# Sheet1.net
KiCad netlist of a schematic drawn in Altium Designer
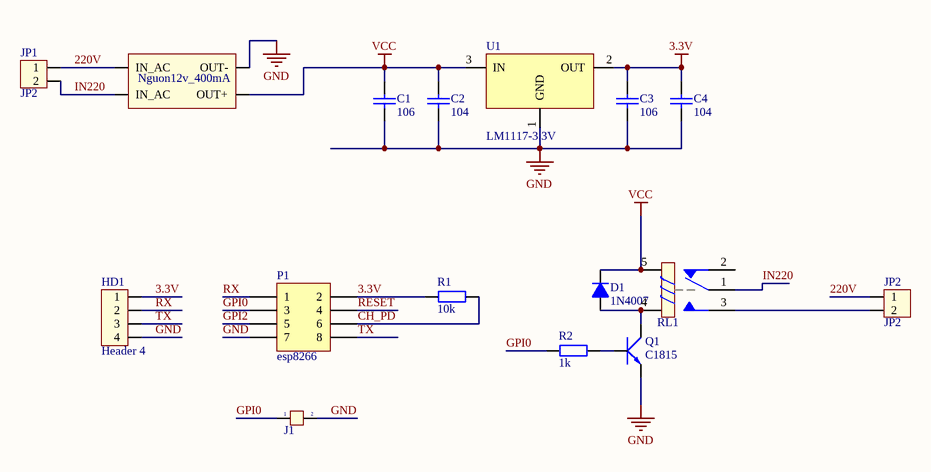
[diagram p0: Sheet1.SchDoc]

(export (version "E")
  (design (tool "Eeschema 10.0.6"))
  (components
    (comp (ref "C1")
      (value "106")
      (footprint "0805_MH")
      (libsource (lib "MH_THU VIEN CHUAN 01-11-2014") (part "CAP 0805"))
    )
    (comp (ref "C2")
      (value "104")
      (footprint "0805_MH")
      (libsource (lib "MH_THU VIEN CHUAN 01-11-2014") (part "CAP 0805"))
    )
    (comp (ref "C3")
      (value "106")
      (footprint "0805_MH")
      (libsource (lib "MH_THU VIEN CHUAN 01-11-2014") (part "CAP 0805"))
    )
    (comp (ref "C4")
      (value "104")
      (footprint "0805_MH")
      (libsource (lib "MH_THU VIEN CHUAN 01-11-2014") (part "CAP 0805"))
    )
    (comp (ref "D1")
      (value "1N4007")
      (footprint "Diode zenner")
      (description "Diode 1A")
      (libsource (lib "MH_THU VIEN CHUAN 01-11-2014") (part "D1A"))
    )
    (comp (ref "HD1")
      (value "Header 4")
      (footprint "Jumper 4")
      (description "Header 4 (Green)")
      (libsource (lib "MH_THU VIEN CHUAN 01-11-2014") (part "Hed4"))
    )
    (comp (ref "J1")
      (value "Jumper 2")
      (footprint "JP2")
      (libsource (lib "MH_THU VIEN CHUAN 01-11-2014") (part "JP 2"))
    )
    (comp (ref "JP1")
      (value "JP2")
      (footprint "CON 2")
      (description "JUMP DON DUC 2.54")
      (libsource (lib "") (part "JUMP 2_1"))
    )
    (comp (ref "JP2")
      (value "JP2")
      (footprint "CON 2")
      (description "JUMP DON DUC 2.54")
      (libsource (lib "Thu Vien Chuan MH") (part "JUMP 2"))
    )
    (comp (ref "NguonKhongVo_1")
      (value "NguonKhongVo_12v_400ma")
      (footprint "NguonKhongVo_12V_400mA")
      (libsource (lib "MH_THU VIEN CHUAN 01-11-2014") (part "NguonKhongVo_12v_400ma"))
    )
    (comp (ref "P1")
      (value "esp8266")
      (footprint "HDR2X4")
      (description "Header, 4-Pin, Dual row")
      (fields (field (name "PUBLISHER") "Altium Limited"))
      (libsource (lib "MH_THU VIEN CHUAN 01-11-2014") (part "Header 4X2"))
    )
    (comp (ref "Q1")
      (value "C1815")
      (footprint "TRAN-LOWPOWER")
      (description "NPN 600mW, ECB")
      (libsource (lib "MH_THU VIEN CHUAN 01-11-2014") (part "C1815"))
    )
    (comp (ref "R1")
      (value "10k")
      (footprint "0805_MH")
      (description "Resistor 1/4W")
      (libsource (lib "MH_THU VIEN CHUAN 01-11-2014") (part "R1/4W"))
    )
    (comp (ref "R2")
      (value "1k")
      (footprint "0805_MH")
      (description "Resistor 1/4W")
      (libsource (lib "MH_THU VIEN CHUAN 01-11-2014") (part "R1/4W"))
    )
    (comp (ref "RL1")
      (value "Relay ?V - 10A")
      (footprint "RELAY5PIN-10A")
      (description "Relay SPDT,10A - 12VDC 5 Pin")
      (libsource (lib "MH_THU VIEN CHUAN 01-11-2014") (part "Relay 10A"))
    )
    (comp (ref "U1")
      (value "LM1117-3.3V")
      (footprint "LM1117-SOP")
      (description "800mA Low-Dropout Linear Regulator")
      (fields (field (name "CREATOR") "Nguyen Ba Bien"))
      (libsource (lib "MH_THU VIEN CHUAN 01-11-2014") (part "LM1117"))
    )
  )
  (nets
    (net (code "1") (name "/220V") (class "Default")
      (node (ref "JP1") (pin "1") (pinfunction "1_1") (pintype "passive"))
      (node (ref "JP2") (pin "1") (pinfunction "1_1") (pintype "passive"))
      (node (ref "NguonKhongVo_1") (pin "1") (pinfunction "IN_AC_1") (pintype "passive"))
    )
    (net (code "3") (name "/CH_PD") (class "Default")
      (node (ref "P1") (pin "6") (pinfunction "6_6") (pintype "passive"))
      (node (ref "R1") (pin "2") (pinfunction "2_2") (pintype "passive"))
    )
    (net (code "4") (name "/GPI0") (class "Default")
      (node (ref "J1") (pin "1") (pinfunction "1_1") (pintype "passive"))
      (node (ref "P1") (pin "3") (pinfunction "3_3") (pintype "passive"))
      (node (ref "R2") (pin "1") (pinfunction "1_1") (pintype "passive"))
    )
    (net (code "5") (name "/GPI2") (class "Default")
      (node (ref "P1") (pin "5") (pinfunction "5_5") (pintype "passive"))
    )
    (net (code "6") (name "/IN220") (class "Default")
      (node (ref "JP1") (pin "2") (pinfunction "2_2") (pintype "passive"))
      (node (ref "NguonKhongVo_1") (pin "2") (pinfunction "IN_AC_2") (pintype "passive"))
      (node (ref "RL1") (pin "1") (pinfunction "1_1") (pintype "passive"))
    )
    (net (code "7") (name "/RESET") (class "Default")
      (node (ref "P1") (pin "4") (pinfunction "4_4") (pintype "passive"))
    )
    (net (code "8") (name "/RX") (class "Default")
      (node (ref "HD1") (pin "2") (pinfunction "2_2") (pintype "passive"))
      (node (ref "P1") (pin "1") (pinfunction "1_1") (pintype "passive"))
    )
    (net (code "9") (name "/TX") (class "Default")
      (node (ref "HD1") (pin "3") (pinfunction "3_3") (pintype "passive"))
      (node (ref "P1") (pin "8") (pinfunction "8_8") (pintype "passive"))
    )
    (net (code "10") (name "3.3V") (class "Default")
      (node (ref "C3") (pin "2") (pinfunction "2_2") (pintype "passive"))
      (node (ref "C4") (pin "2") (pinfunction "2_2") (pintype "passive"))
      (node (ref "HD1") (pin "1") (pinfunction "1_1") (pintype "passive"))
      (node (ref "P1") (pin "2") (pinfunction "2_2") (pintype "passive"))
      (node (ref "R1") (pin "1") (pinfunction "1_1") (pintype "passive"))
      (node (ref "U1") (pin "2") (pinfunction "OUT_2") (pintype "passive"))
    )
    (net (code "11") (name "GND") (class "Default")
      (node (ref "C1") (pin "1") (pinfunction "1_1") (pintype "passive"))
      (node (ref "C2") (pin "1") (pinfunction "1_1") (pintype "passive"))
      (node (ref "C3") (pin "1") (pinfunction "1_1") (pintype "passive"))
      (node (ref "C4") (pin "1") (pinfunction "1_1") (pintype "passive"))
      (node (ref "HD1") (pin "4") (pinfunction "4_4") (pintype "passive"))
      (node (ref "J1") (pin "2") (pinfunction "2_2") (pintype "passive"))
      (node (ref "NguonKhongVo_1") (pin "4") (pinfunction "OUT-_4") (pintype "passive"))
      (node (ref "P1") (pin "7") (pinfunction "7_7") (pintype "passive"))
      (node (ref "Q1") (pin "1") (pinfunction "E_1") (pintype "passive"))
      (node (ref "U1") (pin "1") (pinfunction "GND_1") (pintype "passive"))
    )
    (net (code "12") (name "Net-(D1-A)") (class "Default")
      (node (ref "D1") (pin "1") (pinfunction "A_1") (pintype "passive"))
      (node (ref "Q1") (pin "2") (pinfunction "C_2") (pintype "passive"))
      (node (ref "RL1") (pin "4") (pinfunction "4_4") (pintype "passive"))
    )
    (net (code "13") (name "Net-(JP2-Pad2)") (class "Default")
      (node (ref "JP2") (pin "2") (pinfunction "2_2") (pintype "passive"))
      (node (ref "RL1") (pin "3") (pinfunction "3_3") (pintype "passive"))
    )
    (net (code "14") (name "Net-(Q1-B)") (class "Default")
      (node (ref "Q1") (pin "3") (pinfunction "B_3") (pintype "passive"))
      (node (ref "R2") (pin "2") (pinfunction "2_2") (pintype "passive"))
    )
    (net (code "15") (name "VCC") (class "Default")
      (node (ref "C1") (pin "2") (pinfunction "2_2") (pintype "passive"))
      (node (ref "C2") (pin "2") (pinfunction "2_2") (pintype "passive"))
      (node (ref "D1") (pin "2") (pinfunction "K_2") (pintype "passive"))
      (node (ref "NguonKhongVo_1") (pin "3") (pinfunction "OUT+_3") (pintype "passive"))
      (node (ref "RL1") (pin "5") (pinfunction "5_5") (pintype "passive"))
      (node (ref "U1") (pin "3") (pinfunction "IN_3") (pintype "passive"))
    )
    (net (code "16") (name "unconnected-(RL1-Pad2)") (class "Default")
      (node (ref "RL1") (pin "2") (pinfunction "2_2") (pintype "passive"))
    )
  )
)
